# cSLIM-SA_display.net
KiCad netlist of a schematic drawn in Altium Designer
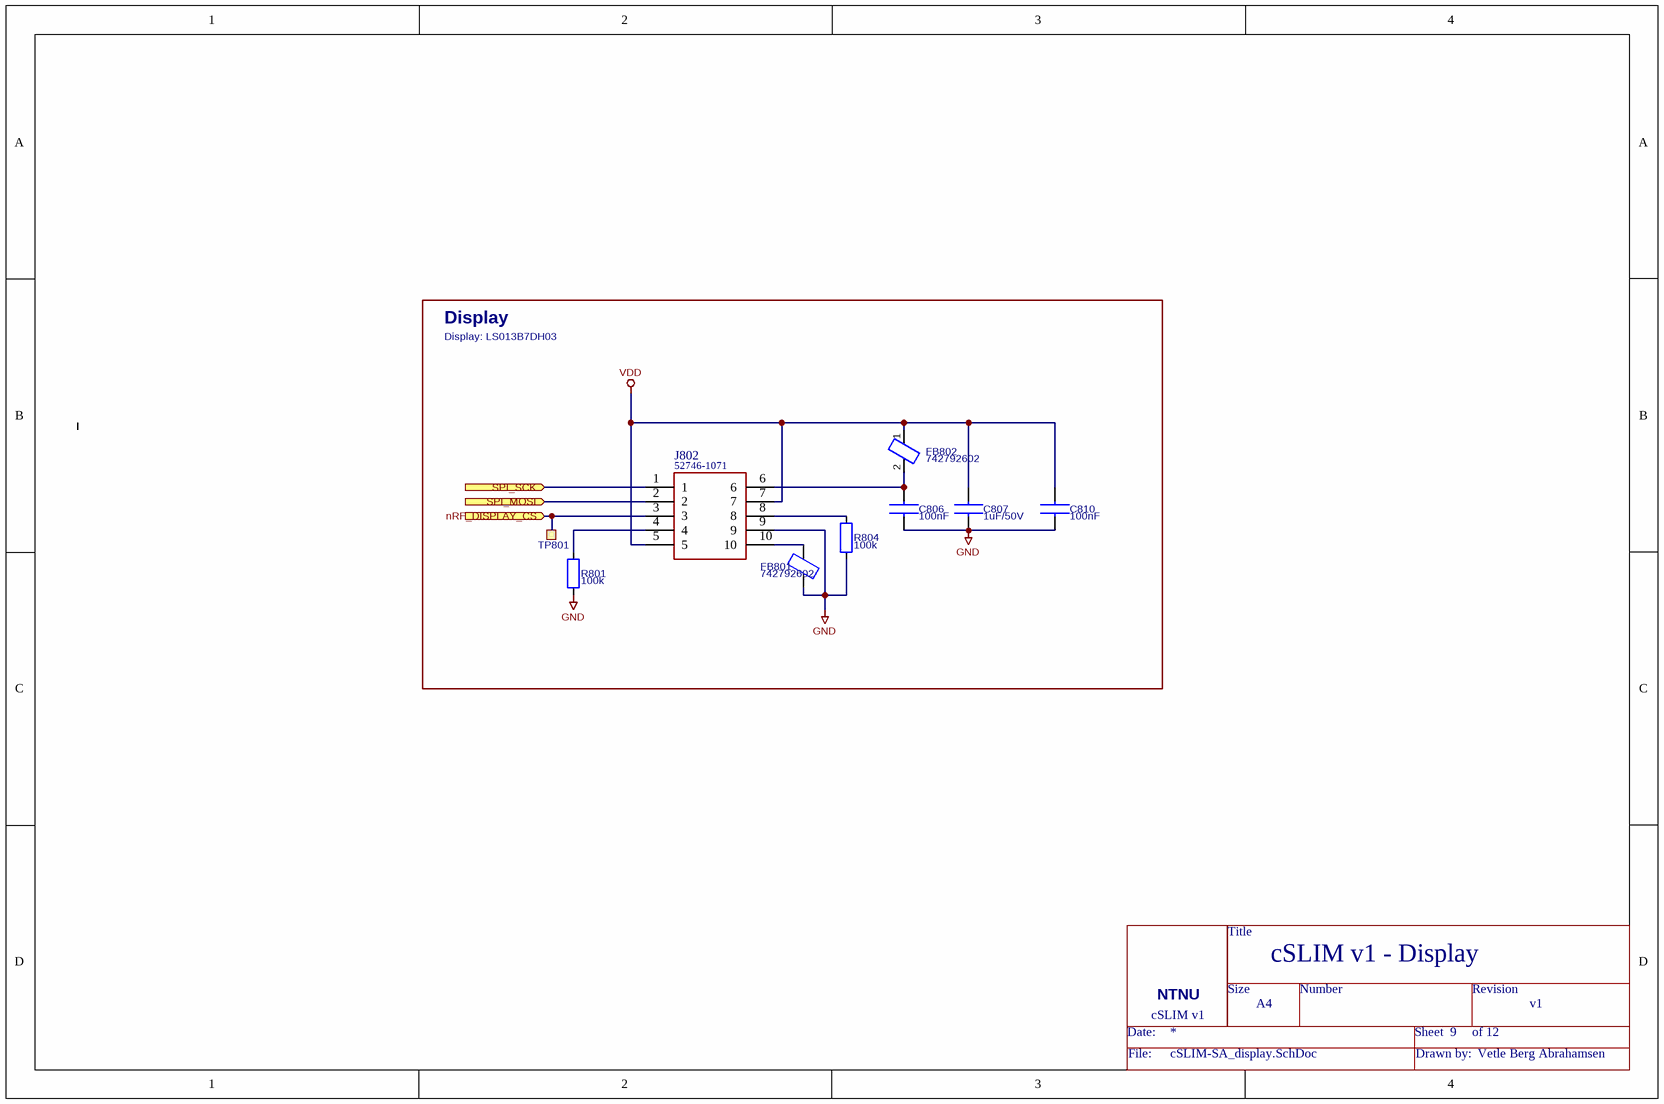
[diagram p0: cSLIM-SA_display.SchDoc]

(export (version "E")
  (design (tool "Eeschema 10.0.6"))
  (components
    (comp (ref "C806")
      (value "100nF")
      (footprint "cSLIM-SA:CAPC1608X90N")
      (description "Capacitor")
      (fields (field (name "MANUFACTURER_PART_NUMBER") "CL10B104KB8NNNL"))
      (libsource (lib "cSLIM-SA") (part "C"))
    )
    (comp (ref "C807")
      (value "1uF/50V")
      (footprint "cSLIM-SA:CAPC1608X90N")
      (description "Capacitor")
      (fields (field (name "MANUFACTURER_PART_NUMBER") "CL10A105KB8NNNC"))
      (libsource (lib "cSLIM-SA") (part "C"))
    )
    (comp (ref "C810")
      (value "100nF")
      (footprint "cSLIM-SA:CAPC1608X90N")
      (description "Capacitor")
      (fields (field (name "MANUFACTURER_PART_NUMBER") "CL10B104KB8NNNL"))
      (libsource (lib "cSLIM-SA") (part "C"))
    )
    (comp (ref "FB801")
      (value "742792602")
      (footprint "CAPC1608X90N")
      (description "Ferrite bead")
      (libsource (lib "") (part "Ferrite_Bead_1"))
    )
    (comp (ref "FB802")
      (value "742792602")
      (footprint "cSLIM-SA:CAPC1608X90N")
      (libsource (lib "cSLIM-SA") (part "Ferrite_Bead"))
    )
    (comp (ref "J802")
      (value "52746-1071")
      (footprint "cSLIM-SA:52746-1071")
      (description "LCD connector \r\nCONN FFC BOTTOM 10POS 0.50MM R/A")
      (fields (field (name "MOUSER PART NUMBER") "538-52746-1071"))
      (libsource (lib "cSLIM-SA") (part "52746-1071"))
    )
    (comp (ref "R801")
      (value "100k")
      (footprint "cSLIM-SA:RESC1608X55N")
      (fields (field (name "MANUFACTURER_PART_NUMBER") "RC0603FR-07100KL"))
      (libsource (lib "cSLIM-SA") (part "R"))
    )
    (comp (ref "R804")
      (value "100k")
      (footprint "cSLIM-SA:RESC1608X55N")
      (fields (field (name "MANUFACTURER_PART_NUMBER") "RC0603FR-07100KL"))
      (libsource (lib "cSLIM-SA") (part "R"))
    )
    (comp (ref "TP801")
      (value "TP")
      (footprint "cSLIM-SA:TP_SMD_Ø1.0mm")
      (description "Test points")
      (libsource (lib "cSLIM-SA") (part "TP"))
    )
  )
  (nets
    (net (code "1") (name "/SPI_MOSI") (class "Default")
      (node (ref "J802") (pin "2") (pinfunction "2_2") (pintype "passive"))
    )
    (net (code "2") (name "/SPI_SCK") (class "Default")
      (node (ref "J802") (pin "1") (pinfunction "1_1") (pintype "passive"))
    )
    (net (code "3") (name "/nRF_DISPLAY_CS") (class "Default")
      (node (ref "J802") (pin "3") (pinfunction "3_3") (pintype "passive"))
      (node (ref "TP801") (pin "1") (pinfunction "1_1") (pintype "passive"))
    )
    (net (code "4") (name "GND") (class "Default")
      (node (ref "C806") (pin "2") (pinfunction "2_2") (pintype "passive"))
      (node (ref "C807") (pin "2") (pinfunction "2_2") (pintype "passive"))
      (node (ref "C810") (pin "2") (pinfunction "2_2") (pintype "passive"))
      (node (ref "FB801") (pin "2") (pinfunction "2_2") (pintype "passive"))
      (node (ref "J802") (pin "9") (pinfunction "9_9") (pintype "passive"))
      (node (ref "R801") (pin "2") (pinfunction "2_2") (pintype "passive"))
      (node (ref "R804") (pin "2") (pinfunction "2_2") (pintype "passive"))
    )
    (net (code "5") (name "Net-(C806-Pad1)") (class "Default")
      (node (ref "C806") (pin "1") (pinfunction "1_1") (pintype "passive"))
      (node (ref "FB802") (pin "2") (pinfunction "2_2") (pintype "passive"))
      (node (ref "J802") (pin "6") (pinfunction "6_6") (pintype "passive"))
    )
    (net (code "6") (name "Net-(FB801-Pad1)") (class "Default")
      (node (ref "FB801") (pin "1") (pinfunction "1_1") (pintype "passive"))
      (node (ref "J802") (pin "10") (pinfunction "10_10") (pintype "passive"))
    )
    (net (code "7") (name "Net-(J802-Pad4)") (class "Default")
      (node (ref "J802") (pin "4") (pinfunction "4_4") (pintype "passive"))
      (node (ref "R801") (pin "1") (pinfunction "1_1") (pintype "passive"))
    )
    (net (code "8") (name "Net-(J802-Pad8)") (class "Default")
      (node (ref "J802") (pin "8") (pinfunction "8_8") (pintype "passive"))
      (node (ref "R804") (pin "1") (pinfunction "1_1") (pintype "passive"))
    )
    (net (code "9") (name "VDD") (class "Default")
      (node (ref "C807") (pin "1") (pinfunction "1_1") (pintype "passive"))
      (node (ref "C810") (pin "1") (pinfunction "1_1") (pintype "passive"))
      (node (ref "FB802") (pin "1") (pinfunction "1_1") (pintype "passive"))
      (node (ref "J802") (pin "5") (pinfunction "5_5") (pintype "passive"))
      (node (ref "J802") (pin "7") (pinfunction "7_7") (pintype "passive"))
    )
  )
)
